# Archimedes_Cevirici_Kati.net
KiCad netlist of a schematic drawn in Altium Designer
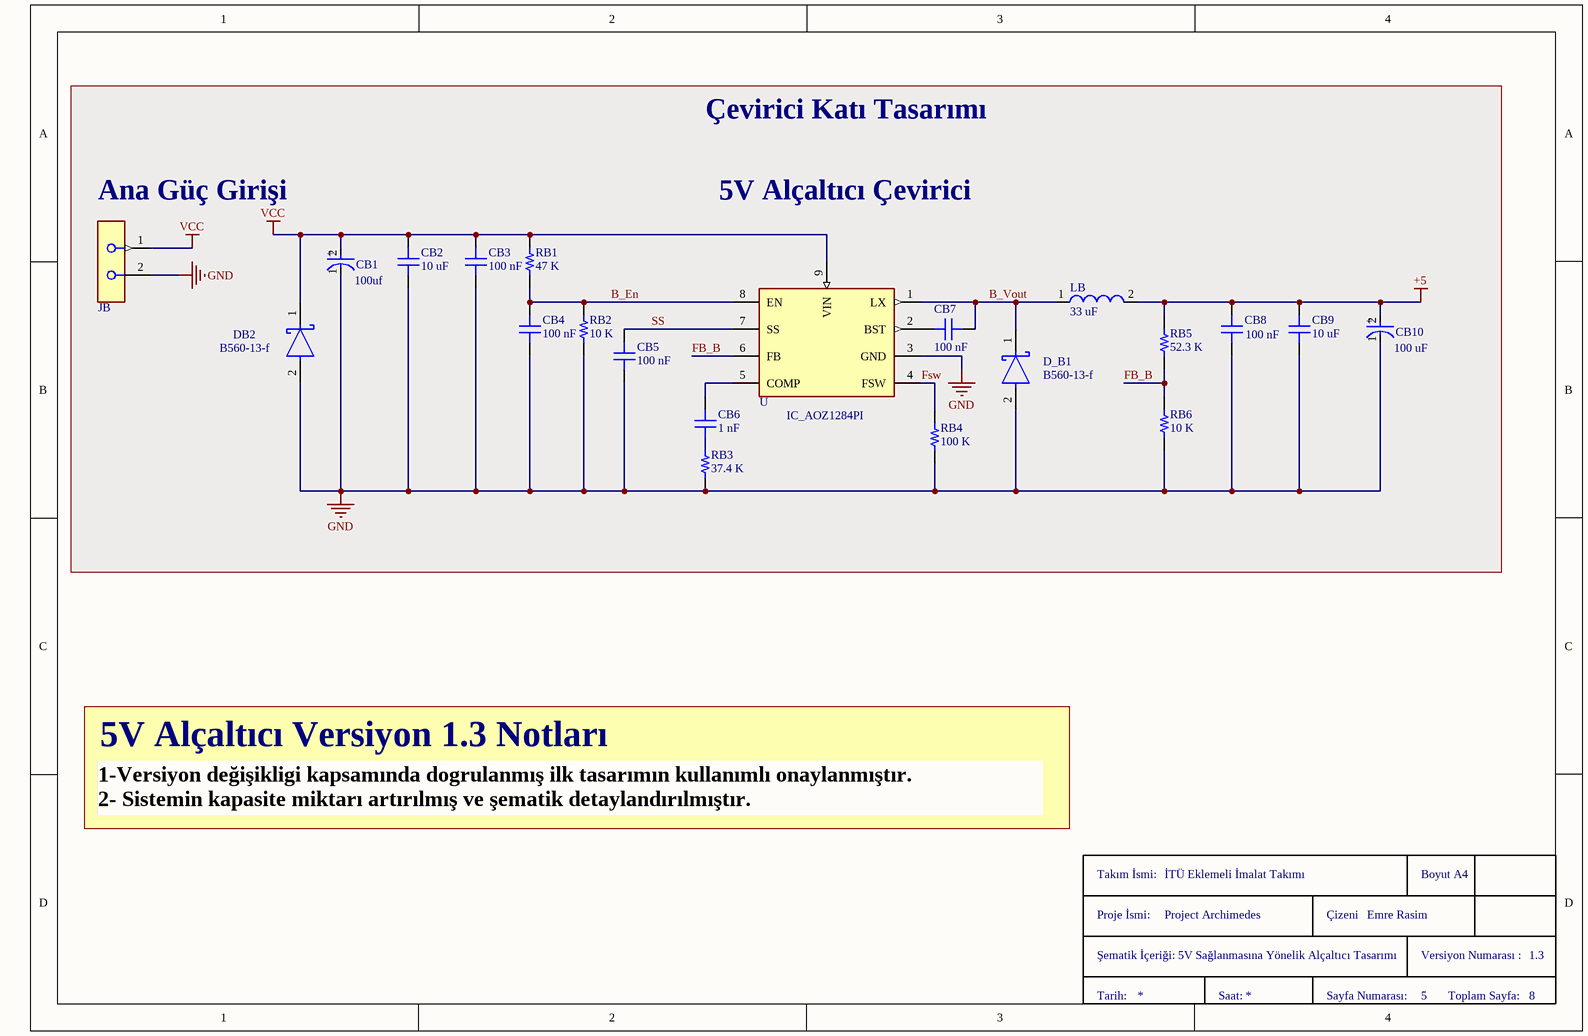
[diagram p0: Archimedes_Cevirici_Kati.SchDoc]

(export (version "E")
  (design (tool "Eeschema 10.0.6"))
  (components
    (comp (ref "CB1")
      (value "100uf")
      (footprint "C_Smd_D6.3_H_7.7_Electrolytic_Cap")
      (description "Electrolytic capacitor with 100 uf and 35 volt rating")
      (libsource (lib "EKIM_Team_Main") (part "C_smd_D6.3_H7.7"))
    )
    (comp (ref "CB2")
      (value "10 uF")
      (footprint "CAP 1206/3216")
      (description "10 uF  and 50 Volt Ceramic Capacitor 1206 pack with X5R rating")
      (libsource (lib "Pasifler") (part "Capacitor 1206"))
    )
    (comp (ref "CB3")
      (value "100 nF")
      (footprint "CAP 0805/2012")
      (description "100 nF  and 50 Volt Ceramic Capacitor 805 pack with X7R rating")
      (libsource (lib "Pasifler") (part "Capacitor 805"))
    )
    (comp (ref "CB4")
      (value "100 nF")
      (footprint "CAP 0805/2012")
      (description "100 nF  and 50 Volt Ceramic Capacitor 805 pack with X7R rating")
      (libsource (lib "Pasifler") (part "Capacitor 805"))
    )
    (comp (ref "CB5")
      (value "100 nF")
      (footprint "CAP 0805/2012")
      (description "100 nF and 50 Volt Ceramic Capacitor 805 pack with X7R rating")
      (libsource (lib "Pasifler") (part "Capacitor 805"))
    )
    (comp (ref "CB6")
      (value "1 nF")
      (footprint "CAP 0805/2012")
      (description "1 nF and 50 Volt Ceramic Capacitor 805 pack with X7R rating")
      (libsource (lib "Pasifler") (part "Capacitor 805"))
    )
    (comp (ref "CB7")
      (value "100 nF")
      (footprint "CAP 0805/2012")
      (description "100 nF  and 50 Volt Ceramic Capacitor 805 pack with X7R rating")
      (libsource (lib "Pasifler") (part "Capacitor 805"))
    )
    (comp (ref "CB8")
      (value "100 nF")
      (footprint "CAP 0805/2012")
      (description "100 nF  and 50 Volt Ceramic Capacitor 805 pack with X7R rating")
      (libsource (lib "Pasifler") (part "Capacitor 805"))
    )
    (comp (ref "CB9")
      (value "10 uF")
      (footprint "CAP 1206/3216")
      (description "10 uF  and 50 V Ceramic Capacitor 1206 pack with X5R rating")
      (libsource (lib "Pasifler") (part "Capacitor 1206"))
    )
    (comp (ref "CB10")
      (value "100 uF")
      (footprint "C_Smd_D6.3_H_7.7_Electrolytic_Cap")
      (description "Electrolytic capacitor with 100 uf and 35 volt rating")
      (libsource (lib "EKIM_Team_Main") (part "C_smd_D6.3_H7.7"))
    )
    (comp (ref "DB2")
      (value "B560-13-f")
      (footprint "D_DO214AB_B560C-13-F")
      (description "Schottky diode with 5A and 60 Volt rating")
      (libsource (lib "EKIM_Team_Main") (part "D_Do214AB_B560-13-F"))
    )
    (comp (ref "D_B1")
      (value "B560-13-f")
      (footprint "D_DO214AB_B560C-13-F")
      (description "Schottky diode with 5A and 60 Volt rating")
      (libsource (lib "EKIM_Team_Main") (part "D_Do214AB_B560-13-F"))
    )
    (comp (ref "JB")
      (value "Con_5mm_2 lead")
      (footprint "Con_5mm_2lead")
      (description "TERM BLOCK 2POS SIDE ENTRY 5MM")
      (libsource (lib "EKIM_Team_Main") (part "Con_5mm_2 lead"))
    )
    (comp (ref "LB")
      (value "33 uF")
      (footprint "L_12*12_33uh_İnductor")
      (description "SMD Flat Wire High Current Inductor WE-HCI, L=33.0 µH")
      (fields (field (name "PARTNUMBER") "74435573300"))
      (libsource (lib "EKIM_Team_Main") (part "L_12_12_33uh_smd_inductor"))
    )
    (comp (ref "RB1")
      (value "47 K")
      (footprint "RES 0805/2012")
      (description "47 K ohm Resistor  with 805 pack and %1 tolerance rating")
      (libsource (lib "Pasifler") (part "Resistor 805"))
    )
    (comp (ref "RB2")
      (value "10 K")
      (footprint "RES 0805/2012")
      (description "10 K ohm Resistor  with 805 pack and %1 tolerance rating")
      (libsource (lib "Pasifler") (part "Resistor 805"))
    )
    (comp (ref "RB3")
      (value "37.4 K")
      (footprint "RES 0805/2012")
      (description "37,4 K ohm Resistor  with 805 pack and %1 tolerance rating")
      (libsource (lib "Pasifler") (part "Resistor 805"))
    )
    (comp (ref "RB4")
      (value "100 K")
      (footprint "RES 0805/2012")
      (description "100 K ohm Resistor  with 805 pack and %1 tolerance rating")
      (libsource (lib "Pasifler") (part "Resistor 805"))
    )
    (comp (ref "RB5")
      (value "52.3 K")
      (footprint "RES 0805/2012")
      (description "52,3 K ohm Resistor  with 805 pack and %1 tolerance rating")
      (libsource (lib "Pasifler") (part "Resistor 805"))
    )
    (comp (ref "RB6")
      (value "10 K")
      (footprint "RES 0805/2012")
      (description "10 K ohm Resistor  with 805 pack and %1 tolerance rating")
      (libsource (lib "Pasifler") (part "Resistor 805"))
    )
    (comp (ref "U")
      (value "IC_AOZ1284PI")
      (footprint "IC_AOZ1284_SOP127P")
      (fields (field (name "MF") "Alpha &") (field (name "MP") "AOZ1284PI"))
      (libsource (lib "EKIM_Team_Main") (part "IC_AOZ1284PI"))
    )
  )
  (nets
    (net (code "1") (name "+5") (class "Default")
      (node (ref "CB10") (pin "2") (pinfunction "A_2") (pintype "passive"))
      (node (ref "CB8") (pin "2") (pinfunction "2_2") (pintype "passive"))
      (node (ref "CB9") (pin "1") (pinfunction "1_1") (pintype "passive"))
      (node (ref "LB") (pin "2") (pinfunction "2_2") (pintype "passive"))
      (node (ref "RB5") (pin "2") (pinfunction "2_2") (pintype "passive"))
    )
    (net (code "2") (name "/B_En") (class "Default")
      (node (ref "CB4") (pin "2") (pinfunction "2_2") (pintype "passive"))
      (node (ref "RB1") (pin "1") (pinfunction "1_1") (pintype "passive"))
      (node (ref "RB2") (pin "2") (pinfunction "2_2") (pintype "passive"))
      (node (ref "U") (pin "8") (pinfunction "EN_8") (pintype "passive"))
    )
    (net (code "3") (name "/B_Vout") (class "Default")
      (node (ref "CB7") (pin "1") (pinfunction "1_1") (pintype "passive"))
      (node (ref "D_B1") (pin "1") (pinfunction "C_1") (pintype "passive"))
      (node (ref "LB") (pin "1") (pinfunction "1_1") (pintype "passive"))
      (node (ref "U") (pin "1") (pinfunction "LX_1") (pintype "output"))
    )
    (net (code "4") (name "/FB_B") (class "Default")
      (node (ref "RB5") (pin "1") (pinfunction "1_1") (pintype "passive"))
      (node (ref "RB6") (pin "2") (pinfunction "2_2") (pintype "passive"))
      (node (ref "U") (pin "6") (pinfunction "FB_6") (pintype "passive"))
    )
    (net (code "5") (name "/Fsw") (class "Default")
      (node (ref "RB4") (pin "2") (pinfunction "2_2") (pintype "passive"))
      (node (ref "U") (pin "4") (pinfunction "FSW_4") (pintype "passive"))
    )
    (net (code "6") (name "/SS") (class "Default")
      (node (ref "CB5") (pin "2") (pinfunction "2_2") (pintype "passive"))
      (node (ref "U") (pin "7") (pinfunction "SS_7") (pintype "passive"))
    )
    (net (code "7") (name "GND") (class "Default")
      (node (ref "CB1") (pin "1") (pinfunction "C_1") (pintype "passive"))
      (node (ref "CB10") (pin "1") (pinfunction "C_1") (pintype "passive"))
      (node (ref "CB2") (pin "2") (pinfunction "2_2") (pintype "passive"))
      (node (ref "CB3") (pin "1") (pinfunction "1_1") (pintype "passive"))
      (node (ref "CB4") (pin "1") (pinfunction "1_1") (pintype "passive"))
      (node (ref "CB5") (pin "1") (pinfunction "1_1") (pintype "passive"))
      (node (ref "CB8") (pin "1") (pinfunction "1_1") (pintype "passive"))
      (node (ref "CB9") (pin "2") (pinfunction "2_2") (pintype "passive"))
      (node (ref "DB2") (pin "2") (pinfunction "A_2") (pintype "passive"))
      (node (ref "D_B1") (pin "2") (pinfunction "A_2") (pintype "passive"))
      (node (ref "JB") (pin "2") (pinfunction "2_2") (pintype "passive"))
      (node (ref "RB2") (pin "1") (pinfunction "1_1") (pintype "passive"))
      (node (ref "RB3") (pin "1") (pinfunction "1_1") (pintype "passive"))
      (node (ref "RB4") (pin "1") (pinfunction "1_1") (pintype "passive"))
      (node (ref "RB6") (pin "1") (pinfunction "1_1") (pintype "passive"))
      (node (ref "U") (pin "3") (pinfunction "GND_3") (pintype "power_in"))
    )
    (net (code "8") (name "Net-(CB6-Pad1)") (class "Default")
      (node (ref "CB6") (pin "1") (pinfunction "1_1") (pintype "passive"))
      (node (ref "RB3") (pin "2") (pinfunction "2_2") (pintype "passive"))
    )
    (net (code "9") (name "Net-(U-BST)") (class "Default")
      (node (ref "CB7") (pin "2") (pinfunction "2_2") (pintype "passive"))
      (node (ref "U") (pin "2") (pinfunction "BST_2") (pintype "output"))
    )
    (net (code "10") (name "Net-(U-COMP)") (class "Default")
      (node (ref "CB6") (pin "2") (pinfunction "2_2") (pintype "passive"))
      (node (ref "U") (pin "5") (pinfunction "COMP_5") (pintype "passive"))
    )
    (net (code "11") (name "VCC") (class "Default")
      (node (ref "CB1") (pin "2") (pinfunction "A_2") (pintype "passive"))
      (node (ref "CB2") (pin "1") (pinfunction "1_1") (pintype "passive"))
      (node (ref "CB3") (pin "2") (pinfunction "2_2") (pintype "passive"))
      (node (ref "DB2") (pin "1") (pinfunction "C_1") (pintype "passive"))
      (node (ref "JB") (pin "1") (pinfunction "1_1") (pintype "output"))
      (node (ref "RB1") (pin "2") (pinfunction "2_2") (pintype "passive"))
      (node (ref "U") (pin "9") (pinfunction "VIN_9") (pintype "input"))
    )
  )
)
